# MJ808_clone_-_rev_5_-_poc.net
KiCad netlist of a schematic drawn in EAGLE
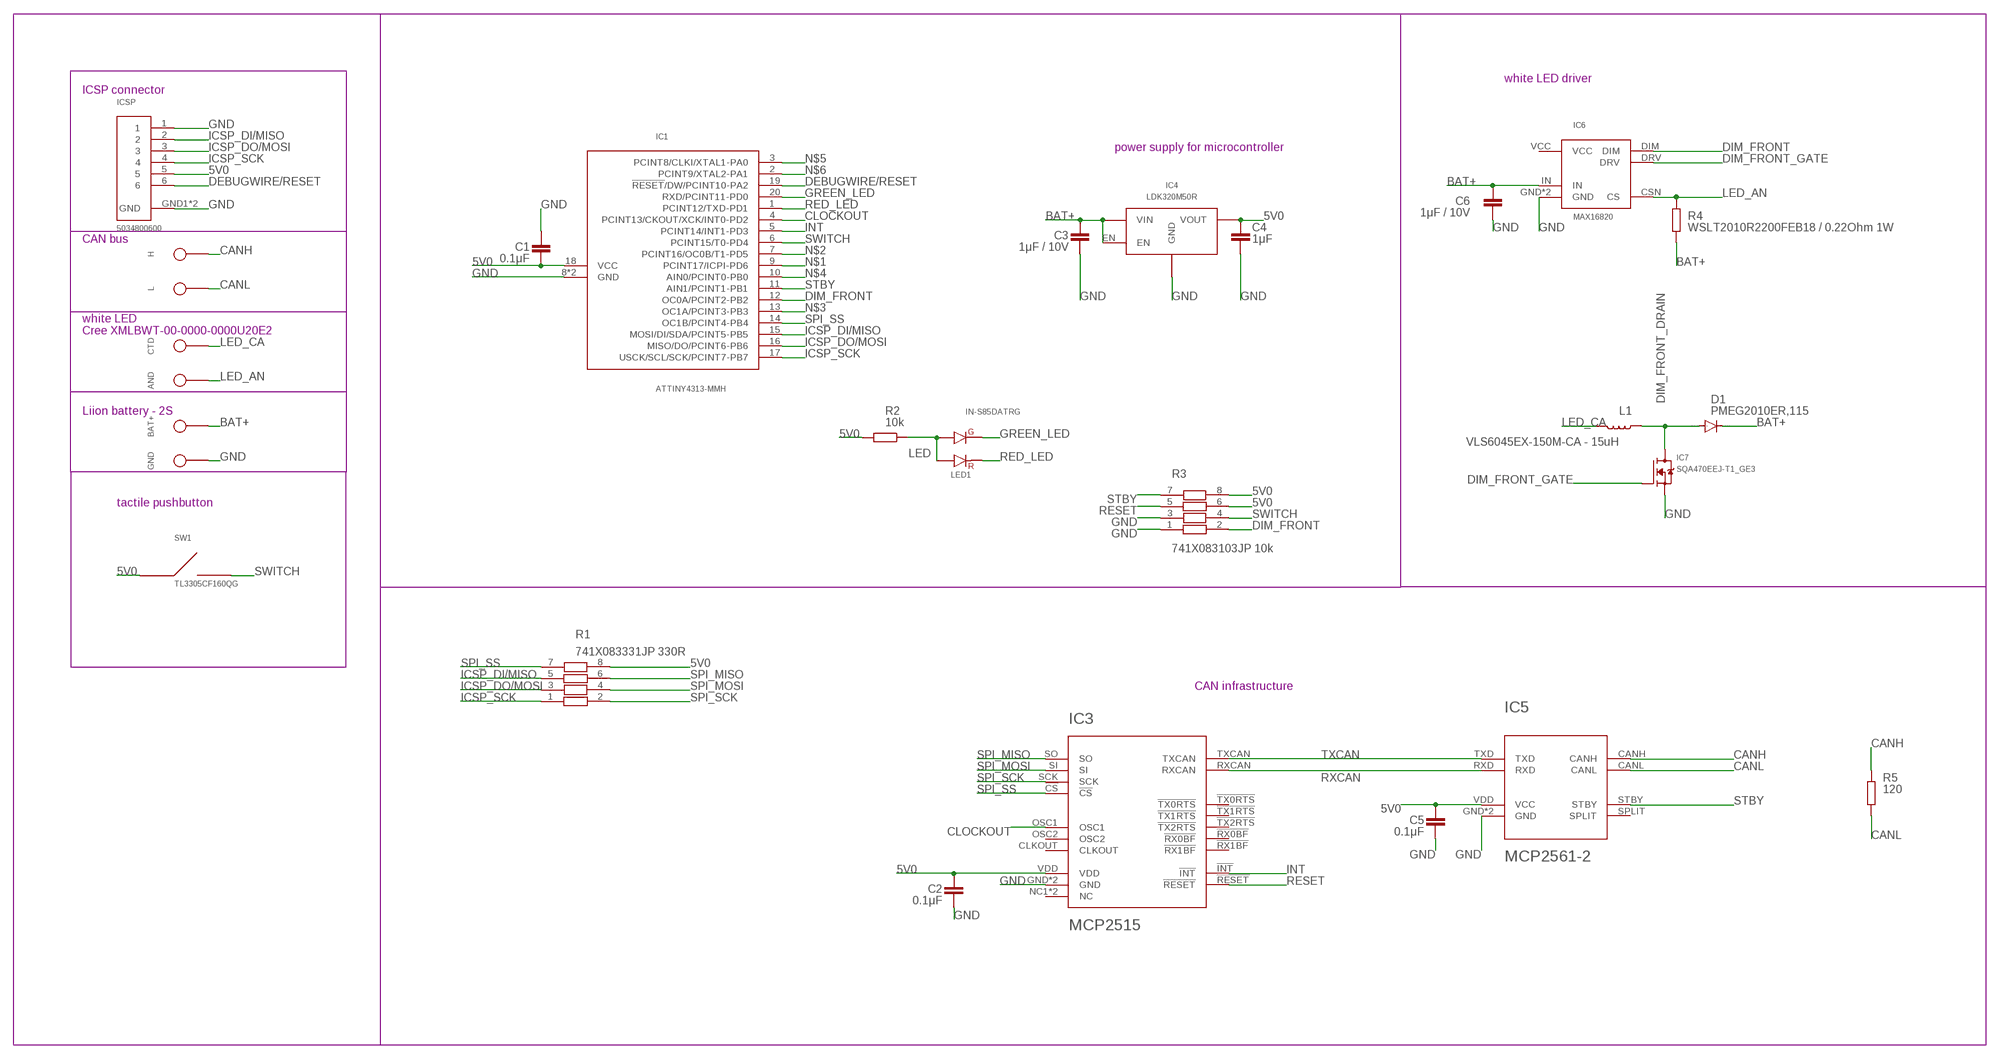
[diagram p0: schematic, sheet 1]

(export (version "E")
  (design (tool "Eeschema 10.0.6"))
  (components
    (comp (ref "AND")
      (value "LED anode")
      (footprint "eagle-import:TH-1.2MM")
      (libsource (lib "eagle-import") (part "TPTH-1.2MM"))
    )
    (comp (ref "BAT+")
      (value "LiIon + Terminal")
      (footprint "eagle-import:TH-1.2MM")
      (libsource (lib "eagle-import") (part "TPTH-1.2MM"))
    )
    (comp (ref "C1")
      (value "0.1μF")
      (footprint "eagle-import:C0402")
      (libsource (lib "eagle-import") (part "C-EUC0402"))
    )
    (comp (ref "C2")
      (value "0.1μF")
      (footprint "eagle-import:C0402")
      (libsource (lib "eagle-import") (part "C-EUC0402"))
    )
    (comp (ref "C3")
      (value "1μF / 10V")
      (footprint "eagle-import:C0402")
      (libsource (lib "eagle-import") (part "C-EUC0402"))
    )
    (comp (ref "C4")
      (value "1μF")
      (footprint "eagle-import:C0402")
      (libsource (lib "eagle-import") (part "C-EUC0402"))
    )
    (comp (ref "C5")
      (value "0.1μF")
      (footprint "eagle-import:C0402")
      (libsource (lib "eagle-import") (part "C-EUC0402"))
    )
    (comp (ref "C6")
      (value "1μF / 10V")
      (footprint "eagle-import:C0402")
      (libsource (lib "eagle-import") (part "C-EUC0402"))
    )
    (comp (ref "CTD")
      (value "LED cathode")
      (footprint "eagle-import:TH-1.2MM")
      (libsource (lib "eagle-import") (part "TPTH-1.2MM"))
    )
    (comp (ref "D1")
      (value "PMEG2010ER,115")
      (footprint "eagle-import:SOD123")
      (libsource (lib "eagle-import") (part "DIODE-SOD123"))
    )
    (comp (ref "GND")
      (value "LiIon - Terminal")
      (footprint "eagle-import:TH-1.2MM")
      (libsource (lib "eagle-import") (part "TPTH-1.2MM"))
    )
    (comp (ref "H")
      (value "CAN high")
      (footprint "eagle-import:TH-1.2MM")
      (libsource (lib "eagle-import") (part "TPTH-1.2MM"))
    )
    (comp (ref "IC1")
      (value "ATTINY4313-MMH")
      (footprint "eagle-import:VQFN-20")
      (fields (field (name "SPICEPREFIX") "X"))
      (libsource (lib "eagle-import") (part "ATTINY4313VQFN-20"))
    )
    (comp (ref "IC3")
      (value "MCP2515")
      (footprint "eagle-import:QFN20")
      (libsource (lib "eagle-import") (part "MCP2515-I-ML"))
    )
    (comp (ref "IC4")
      (value "LDK320M50R")
      (footprint "eagle-import:SOT-23-5L")
      (libsource (lib "eagle-import") (part "LDK320SOT-23-5L"))
    )
    (comp (ref "IC5")
      (value "MCP2561-2")
      (footprint "eagle-import:DFN10")
      (libsource (lib "eagle-import") (part "MCP2561-2"))
    )
    (comp (ref "IC6")
      (value "MAX16820")
      (footprint "eagle-import:TDFN-6-EP")
      (libsource (lib "eagle-import") (part "MAX16820"))
    )
    (comp (ref "IC7")
      (value "SQA470EEJ-T1_GE3")
      (footprint "eagle-import:SC-70-6")
      (libsource (lib "eagle-import") (part "SIA456DJ"))
    )
    (comp (ref "ICSP")
      (value "5034800600")
      (footprint "eagle-import:SMT")
      (libsource (lib "eagle-import") (part "5034800600"))
    )
    (comp (ref "L")
      (value "CAN low")
      (footprint "eagle-import:TH-1.2MM")
      (libsource (lib "eagle-import") (part "TPTH-1.2MM"))
    )
    (comp (ref "L1")
      (value "VLS6045EX-150M-CA - 15uH")
      (footprint "eagle-import:SRN6045")
      (libsource (lib "eagle-import") (part "INDUCTOR-SRN6045-33UH"))
    )
    (comp (ref "LED1")
      (value "IN-S85DATRG")
      (footprint "eagle-import:SMD")
      (libsource (lib "eagle-import") (part "APHBM2012LSURKZGKC"))
    )
    (comp (ref "R1")
      (value "741X083331JP 330R")
      (footprint "eagle-import:0402-4R")
      (libsource (lib "eagle-import") (part "741X083331JP"))
    )
    (comp (ref "R2")
      (value "10k")
      (footprint "eagle-import:R0402")
      (libsource (lib "eagle-import") (part "R-EU_R0402"))
    )
    (comp (ref "R3")
      (value "741X083103JP 10k")
      (footprint "eagle-import:0402-4R")
      (libsource (lib "eagle-import") (part "741X083331JP"))
    )
    (comp (ref "R4")
      (value "WSLT2010R2200FEB18 / 0.22Ohm 1W")
      (footprint "eagle-import:R2010")
      (libsource (lib "eagle-import") (part "R-EU_R2010"))
    )
    (comp (ref "R5")
      (value "120")
      (footprint "eagle-import:R0805")
      (libsource (lib "eagle-import") (part "R-EU_R0805"))
    )
    (comp (ref "SW1")
      (value "TL3305CF160QG")
      (footprint "eagle-import:SMD")
      (libsource (lib "eagle-import") (part "TL3305-844809"))
    )
  )
  (nets
    (net (code "1") (name "/5V0") (class "Default")
      (node (ref "C1") (pin "1") (pinfunction "1_1") (pintype "passive"))
      (node (ref "C2") (pin "1") (pinfunction "1_1") (pintype "passive"))
      (node (ref "C4") (pin "2") (pinfunction "2_2") (pintype "passive"))
      (node (ref "C5") (pin "1") (pinfunction "1_1") (pintype "passive"))
      (node (ref "IC1") (pin "18") (pinfunction "VCC_18") (pintype "bidirectional"))
      (node (ref "IC3") (pin "VDD") (pinfunction "VDD_VDD") (pintype "power_in"))
      (node (ref "IC4") (pin "OUT") (pinfunction "VOUT_OUT") (pintype "bidirectional"))
      (node (ref "IC5") (pin "VDD") (pinfunction "VCC_VDD") (pintype "power_in"))
      (node (ref "ICSP") (pin "5") (pinfunction "5_5") (pintype "bidirectional"))
      (node (ref "R1") (pin "8") (pinfunction "8_8") (pintype "bidirectional"))
      (node (ref "R2") (pin "2") (pinfunction "2_2") (pintype "passive"))
      (node (ref "R3") (pin "6") (pinfunction "6_6") (pintype "bidirectional"))
      (node (ref "R3") (pin "8") (pinfunction "8_8") (pintype "bidirectional"))
      (node (ref "SW1") (pin "1") (pinfunction "P$1_1") (pintype "bidirectional"))
      (node (ref "SW1") (pin "2") (pinfunction "P$1_2") (pintype "bidirectional"))
    )
    (net (code "2") (name "/BAT+") (class "Default")
      (node (ref "BAT+") (pin "TP$1") (pinfunction "TP$1_TP$1") (pintype "bidirectional"))
      (node (ref "C3") (pin "1") (pinfunction "1_1") (pintype "passive"))
      (node (ref "C6") (pin "1") (pinfunction "1_1") (pintype "passive"))
      (node (ref "D1") (pin "C") (pinfunction "C_C") (pintype "passive"))
      (node (ref "IC4") (pin "EN") (pinfunction "EN_EN") (pintype "bidirectional"))
      (node (ref "IC4") (pin "IN") (pinfunction "VIN_IN") (pintype "bidirectional"))
      (node (ref "IC6") (pin "IN") (pinfunction "IN_IN") (pintype "power_in"))
      (node (ref "R4") (pin "2") (pinfunction "2_2") (pintype "passive"))
    )
    (net (code "3") (name "/CANH") (class "Default")
      (node (ref "H") (pin "TP$1") (pinfunction "TP$1_TP$1") (pintype "bidirectional"))
      (node (ref "IC5") (pin "CANH") (pinfunction "CANH_CANH") (pintype "bidirectional"))
      (node (ref "R5") (pin "2") (pinfunction "2_2") (pintype "passive"))
    )
    (net (code "4") (name "/CANL") (class "Default")
      (node (ref "IC5") (pin "CANL") (pinfunction "CANL_CANL") (pintype "bidirectional"))
      (node (ref "L") (pin "TP$1") (pinfunction "TP$1_TP$1") (pintype "bidirectional"))
      (node (ref "R5") (pin "1") (pinfunction "1_1") (pintype "passive"))
    )
    (net (code "5") (name "/CLOCKOUT") (class "Default")
      (node (ref "IC1") (pin "4") (pinfunction "PCINT13/CKOUT/XCK/INT0-PD2_4") (pintype "bidirectional"))
      (node (ref "IC3") (pin "OSC1") (pinfunction "OSC1_OSC1") (pintype "bidirectional"))
    )
    (net (code "6") (name "/DEBUGWIRE{slash}RESET") (class "Default")
      (node (ref "IC1") (pin "19") (pinfunction "~{RESET}/DW/PCINT10-PA2_19") (pintype "bidirectional"))
      (node (ref "ICSP") (pin "6") (pinfunction "6_6") (pintype "bidirectional"))
    )
    (net (code "7") (name "/DIM_FRONT") (class "Default")
      (node (ref "IC1") (pin "12") (pinfunction "OC0A/PCINT2-PB2_12") (pintype "bidirectional"))
      (node (ref "IC6") (pin "DIM") (pinfunction "DIM_DIM") (pintype "bidirectional"))
      (node (ref "R3") (pin "2") (pinfunction "2_2") (pintype "bidirectional"))
    )
    (net (code "8") (name "/DIM_FRONT_DRAIN") (class "Default")
      (node (ref "D1") (pin "A") (pinfunction "A_A") (pintype "passive"))
      (node (ref "IC7") (pin "1D") (pinfunction "D_1D") (pintype "passive"))
      (node (ref "IC7") (pin "2D") (pinfunction "D_2D") (pintype "passive"))
      (node (ref "IC7") (pin "5D") (pinfunction "D_5D") (pintype "passive"))
      (node (ref "IC7") (pin "6D") (pinfunction "D_6D") (pintype "passive"))
      (node (ref "IC7") (pin "D") (pinfunction "D_D") (pintype "passive"))
      (node (ref "L1") (pin "1") (pinfunction "1_1") (pintype "passive"))
    )
    (net (code "9") (name "/DIM_FRONT_GATE") (class "Default")
      (node (ref "IC6") (pin "DRV") (pinfunction "DRV_DRV") (pintype "bidirectional"))
      (node (ref "IC7") (pin "3G") (pinfunction "G_3G") (pintype "passive"))
    )
    (net (code "10") (name "/GND") (class "Default")
      (node (ref "C1") (pin "2") (pinfunction "2_2") (pintype "passive"))
      (node (ref "C2") (pin "2") (pinfunction "2_2") (pintype "passive"))
      (node (ref "C3") (pin "2") (pinfunction "2_2") (pintype "passive"))
      (node (ref "C4") (pin "1") (pinfunction "1_1") (pintype "passive"))
      (node (ref "C5") (pin "2") (pinfunction "2_2") (pintype "passive"))
      (node (ref "C6") (pin "2") (pinfunction "2_2") (pintype "passive"))
      (node (ref "GND") (pin "TP$1") (pinfunction "TP$1_TP$1") (pintype "bidirectional"))
      (node (ref "IC1") (pin "8") (pinfunction "GND_8") (pintype "bidirectional"))
      (node (ref "IC1") (pin "GND") (pinfunction "GND_GND") (pintype "bidirectional"))
      (node (ref "IC3") (pin "GND") (pinfunction "GND_GND") (pintype "power_in"))
      (node (ref "IC3") (pin "GND6") (pinfunction "GND_GND6") (pintype "power_in"))
      (node (ref "IC4") (pin "GND") (pinfunction "GND_GND") (pintype "bidirectional"))
      (node (ref "IC5") (pin "GND") (pinfunction "GND_GND") (pintype "power_in"))
      (node (ref "IC5") (pin "VSS") (pinfunction "GND_VSS") (pintype "power_in"))
      (node (ref "IC6") (pin "GND") (pinfunction "GND_GND") (pintype "power_in"))
      (node (ref "IC6") (pin "GND1") (pinfunction "GND_GND1") (pintype "power_in"))
      (node (ref "IC7") (pin "4S") (pinfunction "S_4S") (pintype "passive"))
      (node (ref "IC7") (pin "S") (pinfunction "S_S") (pintype "passive"))
      (node (ref "ICSP") (pin "1") (pinfunction "1_1") (pintype "bidirectional"))
      (node (ref "ICSP") (pin "GND1") (pinfunction "GND_GND1") (pintype "bidirectional"))
      (node (ref "ICSP") (pin "GND2") (pinfunction "GND_GND2") (pintype "bidirectional"))
      (node (ref "R3") (pin "1") (pinfunction "1_1") (pintype "bidirectional"))
      (node (ref "R3") (pin "3") (pinfunction "3_3") (pintype "bidirectional"))
    )
    (net (code "11") (name "/GREEN_LED") (class "Default")
      (node (ref "IC1") (pin "20") (pinfunction "RXD/PCINT11-PD0_20") (pintype "bidirectional"))
      (node (ref "LED1") (pin "3") (pinfunction "3_3") (pintype "bidirectional"))
    )
    (net (code "12") (name "/ICSP_DI{slash}MISO") (class "Default")
      (node (ref "IC1") (pin "15") (pinfunction "MOSI/DI/SDA/PCINT5-PB5_15") (pintype "bidirectional"))
      (node (ref "ICSP") (pin "2") (pinfunction "2_2") (pintype "bidirectional"))
      (node (ref "R1") (pin "5") (pinfunction "5_5") (pintype "bidirectional"))
    )
    (net (code "13") (name "/ICSP_DO{slash}MOSI") (class "Default")
      (node (ref "IC1") (pin "16") (pinfunction "MISO/DO/PCINT6-PB6_16") (pintype "bidirectional"))
      (node (ref "ICSP") (pin "3") (pinfunction "3_3") (pintype "bidirectional"))
      (node (ref "R1") (pin "3") (pinfunction "3_3") (pintype "bidirectional"))
    )
    (net (code "14") (name "/ICSP_SCK") (class "Default")
      (node (ref "IC1") (pin "17") (pinfunction "USCK/SCL/SCK/PCINT7-PB7_17") (pintype "bidirectional"))
      (node (ref "ICSP") (pin "4") (pinfunction "4_4") (pintype "bidirectional"))
      (node (ref "R1") (pin "1") (pinfunction "1_1") (pintype "bidirectional"))
    )
    (net (code "15") (name "/INT") (class "Default")
      (node (ref "IC1") (pin "5") (pinfunction "PCINT14/INT1-PD3_5") (pintype "bidirectional"))
      (node (ref "IC3") (pin "!INT!") (pinfunction "~{INT}_!INT!") (pintype "bidirectional"))
    )
    (net (code "16") (name "/LED") (class "Default")
      (node (ref "LED1") (pin "1") (pinfunction "1_1") (pintype "bidirectional"))
      (node (ref "LED1") (pin "4") (pinfunction "4_4") (pintype "bidirectional"))
      (node (ref "R2") (pin "1") (pinfunction "1_1") (pintype "passive"))
    )
    (net (code "17") (name "/LED_AN") (class "Default")
      (node (ref "AND") (pin "TP$1") (pinfunction "TP$1_TP$1") (pintype "bidirectional"))
      (node (ref "IC6") (pin "CSN") (pinfunction "CS_CSN") (pintype "bidirectional"))
      (node (ref "R4") (pin "1") (pinfunction "1_1") (pintype "passive"))
    )
    (net (code "18") (name "/LED_CA") (class "Default")
      (node (ref "CTD") (pin "TP$1") (pinfunction "TP$1_TP$1") (pintype "bidirectional"))
      (node (ref "L1") (pin "2") (pinfunction "2_2") (pintype "passive"))
    )
    (net (code "19") (name "/N$1") (class "Default")
      (node (ref "IC1") (pin "9") (pinfunction "PCINT17/ICPI-PD6_9") (pintype "bidirectional"))
    )
    (net (code "20") (name "/N$2") (class "Default")
      (node (ref "IC1") (pin "7") (pinfunction "PCINT16/OC0B/T1-PD5_7") (pintype "bidirectional"))
    )
    (net (code "21") (name "/N$3") (class "Default")
      (node (ref "IC1") (pin "13") (pinfunction "OC1A/PCINT3-PB3_13") (pintype "bidirectional"))
    )
    (net (code "22") (name "/N$4") (class "Default")
      (node (ref "IC1") (pin "10") (pinfunction "AIN0/PCINT0-PB0_10") (pintype "bidirectional"))
    )
    (net (code "23") (name "/N$5") (class "Default")
      (node (ref "IC1") (pin "3") (pinfunction "PCINT8/CLKI/XTAL1-PA0_3") (pintype "bidirectional"))
    )
    (net (code "24") (name "/N$6") (class "Default")
      (node (ref "IC1") (pin "2") (pinfunction "PCINT9/XTAL2-PA1_2") (pintype "bidirectional"))
    )
    (net (code "25") (name "/RED_LED") (class "Default")
      (node (ref "IC1") (pin "1") (pinfunction "PCINT12/TXD-PD1_1") (pintype "bidirectional"))
      (node (ref "LED1") (pin "2") (pinfunction "2_2") (pintype "bidirectional"))
    )
    (net (code "26") (name "/RESET") (class "Default")
      (node (ref "IC3") (pin "!RESET!") (pinfunction "~{RESET}_!RESET!") (pintype "bidirectional"))
      (node (ref "R3") (pin "5") (pinfunction "5_5") (pintype "bidirectional"))
    )
    (net (code "27") (name "/RXCAN") (class "Default")
      (node (ref "IC3") (pin "RXCAN") (pinfunction "RXCAN_RXCAN") (pintype "input"))
      (node (ref "IC5") (pin "RXD") (pinfunction "RXD_RXD") (pintype "output"))
    )
    (net (code "28") (name "/SPI_MISO") (class "Default")
      (node (ref "IC3") (pin "SO") (pinfunction "SO_SO") (pintype "output"))
      (node (ref "R1") (pin "6") (pinfunction "6_6") (pintype "bidirectional"))
    )
    (net (code "29") (name "/SPI_MOSI") (class "Default")
      (node (ref "IC3") (pin "SI") (pinfunction "SI_SI") (pintype "input"))
      (node (ref "R1") (pin "4") (pinfunction "4_4") (pintype "bidirectional"))
    )
    (net (code "30") (name "/SPI_SCK") (class "Default")
      (node (ref "IC3") (pin "SCK") (pinfunction "SCK_SCK") (pintype "bidirectional"))
      (node (ref "R1") (pin "2") (pinfunction "2_2") (pintype "bidirectional"))
    )
    (net (code "31") (name "/SPI_SS") (class "Default")
      (node (ref "IC1") (pin "14") (pinfunction "OC1B/PCINT4-PB4_14") (pintype "bidirectional"))
      (node (ref "IC3") (pin "!CS!") (pinfunction "~{CS}_!CS!") (pintype "bidirectional"))
      (node (ref "R1") (pin "7") (pinfunction "7_7") (pintype "bidirectional"))
    )
    (net (code "32") (name "/STBY") (class "Default")
      (node (ref "IC1") (pin "11") (pinfunction "AIN1/PCINT1-PB1_11") (pintype "bidirectional"))
      (node (ref "IC5") (pin "STBY") (pinfunction "STBY_STBY") (pintype "bidirectional"))
      (node (ref "R3") (pin "7") (pinfunction "7_7") (pintype "bidirectional"))
    )
    (net (code "33") (name "/SWITCH") (class "Default")
      (node (ref "IC1") (pin "6") (pinfunction "PCINT15/T0-PD4_6") (pintype "bidirectional"))
      (node (ref "R3") (pin "4") (pinfunction "4_4") (pintype "bidirectional"))
      (node (ref "SW1") (pin "3") (pinfunction "P$2_3") (pintype "bidirectional"))
      (node (ref "SW1") (pin "4") (pinfunction "P$2_4") (pintype "bidirectional"))
    )
    (net (code "34") (name "/TXCAN") (class "Default")
      (node (ref "IC3") (pin "TXCAN") (pinfunction "TXCAN_TXCAN") (pintype "output"))
      (node (ref "IC5") (pin "TXD") (pinfunction "TXD_TXD") (pintype "input"))
    )
    (net (code "35") (name "/VCC") (class "Default")
      (node (ref "IC6") (pin "VCC") (pinfunction "VCC_VCC") (pintype "power_in"))
    )
    (net (code "36") (name "unconnected-(IC3-NC-PadNC1)") (class "Default")
      (node (ref "IC3") (pin "NC1") (pinfunction "NC_NC1") (pintype "no_connect"))
    )
    (net (code "37") (name "unconnected-(IC3-NC-PadNC2)") (class "Default")
      (node (ref "IC3") (pin "NC2") (pinfunction "NC_NC2") (pintype "no_connect"))
    )
    (net (code "38") (name "unconnected-(IC3-PadCLKOUT)") (class "Default")
      (node (ref "IC3") (pin "CLKOUT") (pinfunction "CLKOUT_CLKOUT") (pintype "bidirectional"))
    )
    (net (code "39") (name "unconnected-(IC3-PadOSC2)") (class "Default")
      (node (ref "IC3") (pin "OSC2") (pinfunction "OSC2_OSC2") (pintype "bidirectional"))
    )
    (net (code "40") (name "unconnected-(IC3-~{RX0BF}-Pad!RX0BF!)") (class "Default")
      (node (ref "IC3") (pin "!RX0BF!") (pinfunction "~{RX0BF}_!RX0BF!") (pintype "bidirectional"))
    )
    (net (code "41") (name "unconnected-(IC3-~{RX1BF}-Pad!RX1BF!)") (class "Default")
      (node (ref "IC3") (pin "!RX1BF!") (pinfunction "~{RX1BF}_!RX1BF!") (pintype "bidirectional"))
    )
    (net (code "42") (name "unconnected-(IC3-~{TX0RTS}-Pad!TX0RTS!)") (class "Default")
      (node (ref "IC3") (pin "!TX0RTS!") (pinfunction "~{TX0RTS}_!TX0RTS!") (pintype "bidirectional"))
    )
    (net (code "43") (name "unconnected-(IC3-~{TX1RTS}-Pad!TX1RTS!)") (class "Default")
      (node (ref "IC3") (pin "!TX1RTS!") (pinfunction "~{TX1RTS}_!TX1RTS!") (pintype "bidirectional"))
    )
    (net (code "44") (name "unconnected-(IC3-~{TX2RTS}-Pad!TX2RTS!)") (class "Default")
      (node (ref "IC3") (pin "!TX2RTS!") (pinfunction "~{TX2RTS}_!TX2RTS!") (pintype "bidirectional"))
    )
    (net (code "45") (name "unconnected-(IC5-PadSPLIT)") (class "Default")
      (node (ref "IC5") (pin "SPLIT") (pinfunction "SPLIT_SPLIT") (pintype "bidirectional"))
    )
  )
)
